# 19V_Converter.net
KiCad netlist of a schematic drawn in Altium Designer
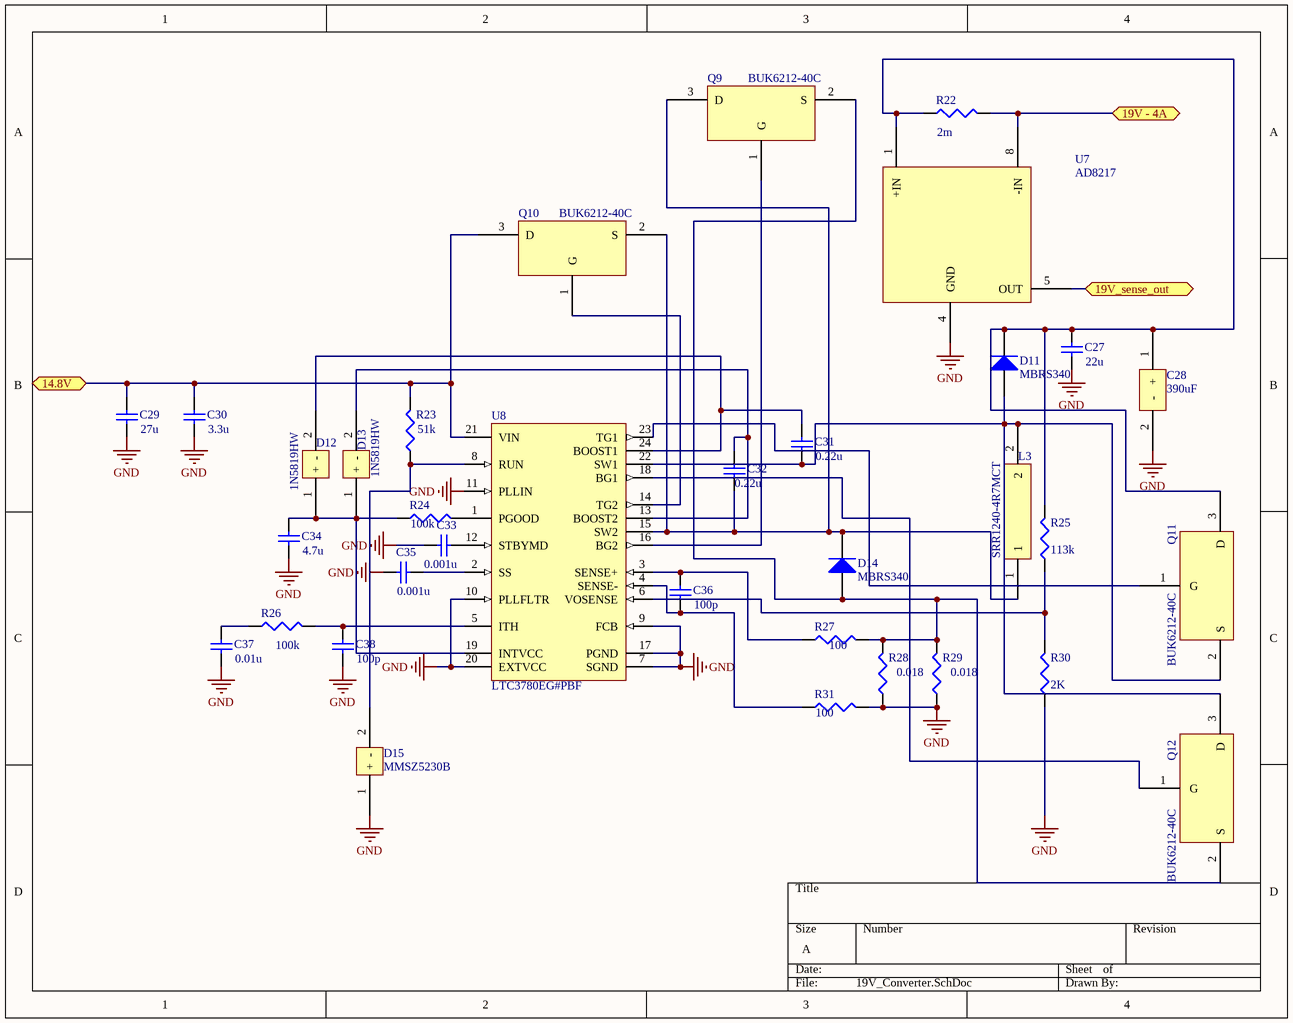
[diagram p0: 19V_Converter.SchDoc]

(export (version "E")
  (design (tool "Eeschema 10.0.6"))
  (components
    (comp (ref "C27")
      (value "22u")
      (footprint "C1206")
      (description "Capacitor (Semiconductor SIM Model)")
      (fields (field (name "Comment") "Cap Semi") (field (name "PUBLISHER") "Altium Limited"))
      (libsource (lib "Miscellaneous Devices") (part "Cap Semi"))
    )
    (comp (ref "C28")
      (value "390uF")
      (footprint "PCV1E391MCL2GS")
      (description "Aluminum Capacitor")
      (libsource (lib "Integrated_Library") (part "PCV1E391MCL2GS"))
    )
    (comp (ref "C29")
      (value "27u")
      (footprint "C1206")
      (description "Capacitor (Semiconductor SIM Model)")
      (fields (field (name "Comment") "Cap Semi") (field (name "PUBLISHER") "Altium Limited"))
      (libsource (lib "Miscellaneous Devices") (part "Cap Semi"))
    )
    (comp (ref "C30")
      (value "3.3u")
      (footprint "C1206")
      (description "Capacitor (Semiconductor SIM Model)")
      (fields (field (name "Comment") "Cap Semi") (field (name "PUBLISHER") "Altium Limited"))
      (libsource (lib "Miscellaneous Devices") (part "Cap Semi"))
    )
    (comp (ref "C31")
      (value "0.22u")
      (footprint "C1206")
      (description "Capacitor (Semiconductor SIM Model)")
      (fields (field (name "Comment") "Cap Semi") (field (name "PUBLISHER") "Altium Limited"))
      (libsource (lib "Miscellaneous Devices") (part "Cap Semi"))
    )
    (comp (ref "C32")
      (value "0.22u")
      (footprint "C1206")
      (description "Capacitor (Semiconductor SIM Model)")
      (fields (field (name "Comment") "Cap Semi") (field (name "PUBLISHER") "Altium Limited"))
      (libsource (lib "Miscellaneous Devices") (part "Cap Semi"))
    )
    (comp (ref "C33")
      (value "0.001u")
      (footprint "C1206")
      (description "Capacitor (Semiconductor SIM Model)")
      (fields (field (name "Comment") "Cap Semi") (field (name "PUBLISHER") "Altium Limited"))
      (libsource (lib "Miscellaneous Devices") (part "Cap Semi"))
    )
    (comp (ref "C34")
      (value "4.7u")
      (footprint "C1206")
      (description "Capacitor (Semiconductor SIM Model)")
      (fields (field (name "Comment") "Cap Semi") (field (name "PUBLISHER") "Altium Limited"))
      (libsource (lib "Miscellaneous Devices") (part "Cap Semi"))
    )
    (comp (ref "C35")
      (value "0.001u")
      (footprint "C1206")
      (description "Capacitor (Semiconductor SIM Model)")
      (fields (field (name "Comment") "Cap Semi") (field (name "PUBLISHER") "Altium Limited"))
      (libsource (lib "Miscellaneous Devices") (part "Cap Semi"))
    )
    (comp (ref "C36")
      (value "100p")
      (footprint "C1206")
      (description "Capacitor (Semiconductor SIM Model)")
      (fields (field (name "Comment") "Cap Semi") (field (name "PUBLISHER") "Altium Limited"))
      (libsource (lib "Miscellaneous Devices") (part "Cap Semi"))
    )
    (comp (ref "C37")
      (value "0.01u")
      (footprint "C1206")
      (description "Capacitor (Semiconductor SIM Model)")
      (fields (field (name "Comment") "Cap Semi") (field (name "PUBLISHER") "Altium Limited"))
      (libsource (lib "Miscellaneous Devices") (part "Cap Semi"))
    )
    (comp (ref "C38")
      (value "100p")
      (footprint "C1206")
      (description "Capacitor (Semiconductor SIM Model)")
      (fields (field (name "Comment") "Cap Semi") (field (name "PUBLISHER") "Altium Limited"))
      (libsource (lib "Miscellaneous Devices") (part "Cap Semi"))
    )
    (comp (ref "D11")
      (value "MBRS340")
      (footprint "SMC")
      (description "Default Diode")
      (fields (field (name "PUBLISHER") "Altium Limited"))
      (libsource (lib "Miscellaneous Devices") (part "Diode"))
    )
    (comp (ref "D12")
      (value "1N5819HW")
      (footprint "1N5819HW")
      (description "1A Schottky Barrier Rectifier")
      (libsource (lib "Integrated_Library") (part "1N5819HW"))
    )
    (comp (ref "D13")
      (value "1N5819HW")
      (footprint "1N5819HW")
      (description "1A Schottky Barrier Rectifier")
      (libsource (lib "Integrated_Library") (part "1N5819HW"))
    )
    (comp (ref "D14")
      (value "MBRS340")
      (footprint "SMC")
      (description "Default Diode")
      (fields (field (name "PUBLISHER") "Altium Limited"))
      (libsource (lib "Miscellaneous Devices") (part "Diode"))
    )
    (comp (ref "D15")
      (value "MMSZ5230B")
      (footprint "MMSZ5230B")
      (description "Zener Diode")
      (libsource (lib "Integrated_Library") (part "MMSZ5230B"))
    )
    (comp (ref "L3")
      (value "SRR1240-4R7MCT")
      (footprint "SRR1240-4R7M")
      (description "Inductor")
      (libsource (lib "Integrated_Library") (part "SRR1240-4R7MCT"))
    )
    (comp (ref "Q9")
      (value "BUK6212-40C")
      (footprint "BUK6212-40C")
      (description "N-Channel TrenchMOS Intermediate Level FET")
      (libsource (lib "Integrated_Library") (part "BUK6212-40C"))
    )
    (comp (ref "Q10")
      (value "BUK6212-40C")
      (footprint "BUK6212-40C")
      (description "N-Channel TrenchMOS Intermediate Level FET")
      (libsource (lib "Integrated_Library") (part "BUK6212-40C"))
    )
    (comp (ref "Q11")
      (value "BUK6212-40C")
      (footprint "BUK6212-40C")
      (description "N-Channel TrenchMOS Intermediate Level FET")
      (libsource (lib "") (part "BUK6212-40C_1"))
    )
    (comp (ref "Q12")
      (value "BUK6212-40C")
      (footprint "BUK6212-40C")
      (description "N-Channel TrenchMOS Intermediate Level FET")
      (libsource (lib "") (part "BUK6212-40C_1"))
    )
    (comp (ref "R22")
      (value "2m")
      (footprint "J1-0603")
      (description "Resistor")
      (fields (field (name "Comment") "Res3") (field (name "PUBLISHER") "Altium Limited"))
      (libsource (lib "Miscellaneous Devices") (part "Res3"))
    )
    (comp (ref "R23")
      (value "51k")
      (footprint "J1-0603")
      (description "Resistor")
      (fields (field (name "Comment") "Res3") (field (name "PUBLISHER") "Altium Limited"))
      (libsource (lib "Miscellaneous Devices") (part "Res3"))
    )
    (comp (ref "R24")
      (value "100k")
      (footprint "J1-0603")
      (description "Resistor")
      (fields (field (name "Comment") "Res3") (field (name "PUBLISHER") "Altium Limited"))
      (libsource (lib "Miscellaneous Devices") (part "Res3"))
    )
    (comp (ref "R25")
      (value "113k")
      (footprint "J1-0603")
      (description "Resistor")
      (fields (field (name "Comment") "Res3") (field (name "PUBLISHER") "Altium Limited"))
      (libsource (lib "Miscellaneous Devices") (part "Res3"))
    )
    (comp (ref "R26")
      (value "100k")
      (footprint "J1-0603")
      (description "Resistor")
      (fields (field (name "Comment") "Res3") (field (name "PUBLISHER") "Altium Limited"))
      (libsource (lib "Miscellaneous Devices") (part "Res3"))
    )
    (comp (ref "R27")
      (value "100")
      (footprint "J1-0603")
      (description "Resistor")
      (fields (field (name "Comment") "Res3") (field (name "PUBLISHER") "Altium Limited"))
      (libsource (lib "Miscellaneous Devices") (part "Res3"))
    )
    (comp (ref "R28")
      (value "0.018")
      (footprint "J1-0603")
      (description "Resistor")
      (fields (field (name "Comment") "Res3") (field (name "PUBLISHER") "Altium Limited"))
      (libsource (lib "Miscellaneous Devices") (part "Res3"))
    )
    (comp (ref "R29")
      (value "0.018")
      (footprint "J1-0603")
      (description "Resistor")
      (fields (field (name "Comment") "Res3") (field (name "PUBLISHER") "Altium Limited"))
      (libsource (lib "Miscellaneous Devices") (part "Res3"))
    )
    (comp (ref "R30")
      (value "2K")
      (footprint "J1-0603")
      (description "Resistor")
      (fields (field (name "Comment") "Res3") (field (name "PUBLISHER") "Altium Limited"))
      (libsource (lib "Miscellaneous Devices") (part "Res3"))
    )
    (comp (ref "R31")
      (value "100")
      (footprint "J1-0603")
      (description "Resistor")
      (fields (field (name "Comment") "Res3") (field (name "PUBLISHER") "Altium Limited"))
      (libsource (lib "Miscellaneous Devices") (part "Res3"))
    )
    (comp (ref "U7")
      (value "AD8217")
      (footprint "AD8217")
      (description "Current Shunt Moniter")
      (libsource (lib "Integrated_Library") (part "AD8217"))
    )
    (comp (ref "U8")
      (value "LTC3780EG#PBF")
      (footprint "LTC3780 24-Leaqd Plastic SSOP")
      (fields (field (name "MANUFACTURER") "Linear Technology"))
      (libsource (lib "Integrated_Library") (part "LTC3780EG#PBF"))
    )
  )
  (nets
    (net (code "1") (name "/14.8V") (class "Default")
      (node (ref "C29") (pin "2") (pinfunction "2_2") (pintype "passive"))
      (node (ref "C30") (pin "2") (pinfunction "2_2") (pintype "passive"))
      (node (ref "Q10") (pin "3") (pinfunction "D_3") (pintype "passive"))
      (node (ref "R23") (pin "2") (pinfunction "2_2") (pintype "passive"))
      (node (ref "U8") (pin "21") (pinfunction "VIN_21") (pintype "power_in"))
    )
    (net (code "2") (name "/19V - 4A") (class "Default")
      (node (ref "R22") (pin "2") (pinfunction "2_2") (pintype "passive"))
      (node (ref "U7") (pin "8") (pinfunction "-IN_8") (pintype "passive"))
    )
    (net (code "3") (name "/19V_sense_out") (class "Default")
      (node (ref "U7") (pin "5") (pinfunction "OUT_5") (pintype "passive"))
    )
    (net (code "4") (name "GND") (class "Default")
      (node (ref "C27") (pin "1") (pinfunction "1_1") (pintype "passive"))
      (node (ref "C28") (pin "2") (pinfunction "-_2") (pintype "passive"))
      (node (ref "C29") (pin "1") (pinfunction "1_1") (pintype "passive"))
      (node (ref "C30") (pin "1") (pinfunction "1_1") (pintype "passive"))
      (node (ref "C33") (pin "1") (pinfunction "1_1") (pintype "passive"))
      (node (ref "C34") (pin "1") (pinfunction "1_1") (pintype "passive"))
      (node (ref "C35") (pin "1") (pinfunction "1_1") (pintype "passive"))
      (node (ref "C37") (pin "1") (pinfunction "1_1") (pintype "passive"))
      (node (ref "C38") (pin "1") (pinfunction "1_1") (pintype "passive"))
      (node (ref "D15") (pin "1") (pinfunction "+_1") (pintype "passive"))
      (node (ref "R28") (pin "1") (pinfunction "1_1") (pintype "passive"))
      (node (ref "R29") (pin "1") (pinfunction "1_1") (pintype "passive"))
      (node (ref "R30") (pin "1") (pinfunction "1_1") (pintype "passive"))
      (node (ref "R31") (pin "2") (pinfunction "2_2") (pintype "passive"))
      (node (ref "U7") (pin "4") (pinfunction "GND_4") (pintype "passive"))
      (node (ref "U8") (pin "10") (pinfunction "PLLFLTR_10") (pintype "input"))
      (node (ref "U8") (pin "11") (pinfunction "PLLIN_11") (pintype "input"))
      (node (ref "U8") (pin "17") (pinfunction "PGND_17") (pintype "power_in"))
      (node (ref "U8") (pin "20") (pinfunction "EXTVCC_20") (pintype "power_in"))
      (node (ref "U8") (pin "7") (pinfunction "SGND_7") (pintype "power_in"))
      (node (ref "U8") (pin "9") (pinfunction "FCB_9") (pintype "input"))
    )
    (net (code "5") (name "Net-(C28-+)") (class "Default")
      (node (ref "C27") (pin "2") (pinfunction "2_2") (pintype "passive"))
      (node (ref "C28") (pin "1") (pinfunction "+_1") (pintype "passive"))
      (node (ref "D11") (pin "2") (pinfunction "K_2") (pintype "passive"))
      (node (ref "Q11") (pin "3") (pinfunction "D_3") (pintype "passive"))
      (node (ref "R22") (pin "1") (pinfunction "1_1") (pintype "passive"))
      (node (ref "R25") (pin "2") (pinfunction "2_2") (pintype "passive"))
      (node (ref "U7") (pin "1") (pinfunction "+IN_1") (pintype "passive"))
    )
    (net (code "6") (name "Net-(C37-Pad2)") (class "Default")
      (node (ref "C37") (pin "2") (pinfunction "2_2") (pintype "passive"))
      (node (ref "R26") (pin "1") (pinfunction "1_1") (pintype "passive"))
    )
    (net (code "7") (name "Net-(D11-A)") (class "Default")
      (node (ref "C31") (pin "1") (pinfunction "1_1") (pintype "passive"))
      (node (ref "D11") (pin "1") (pinfunction "A_1") (pintype "passive"))
      (node (ref "L3") (pin "2") (pinfunction "2_2") (pintype "passive"))
      (node (ref "Q11") (pin "2") (pinfunction "S_2") (pintype "passive"))
      (node (ref "Q12") (pin "3") (pinfunction "D_3") (pintype "passive"))
      (node (ref "U8") (pin "22") (pinfunction "SW1_22") (pintype "passive"))
    )
    (net (code "8") (name "Net-(D12-+)") (class "Default")
      (node (ref "C34") (pin "2") (pinfunction "2_2") (pintype "passive"))
      (node (ref "D12") (pin "1") (pinfunction "+_1") (pintype "passive"))
      (node (ref "D13") (pin "1") (pinfunction "+_1") (pintype "passive"))
      (node (ref "R24") (pin "1") (pinfunction "1_1") (pintype "passive"))
      (node (ref "U8") (pin "19") (pinfunction "INTVCC_19") (pintype "power_in"))
    )
    (net (code "9") (name "Net-(D12--)") (class "Default")
      (node (ref "C31") (pin "2") (pinfunction "2_2") (pintype "passive"))
      (node (ref "D12") (pin "2") (pinfunction "-_2") (pintype "passive"))
      (node (ref "U8") (pin "24") (pinfunction "BOOST1_24") (pintype "passive"))
    )
    (net (code "10") (name "Net-(D13--)") (class "Default")
      (node (ref "C32") (pin "2") (pinfunction "2_2") (pintype "passive"))
      (node (ref "D13") (pin "2") (pinfunction "-_2") (pintype "passive"))
      (node (ref "U8") (pin "13") (pinfunction "BOOST2_13") (pintype "passive"))
    )
    (net (code "11") (name "Net-(D14-A)") (class "Default")
      (node (ref "D14") (pin "1") (pinfunction "A_1") (pintype "passive"))
      (node (ref "Q12") (pin "2") (pinfunction "S_2") (pintype "passive"))
      (node (ref "Q9") (pin "2") (pinfunction "S_2") (pintype "passive"))
      (node (ref "R27") (pin "2") (pinfunction "2_2") (pintype "passive"))
      (node (ref "R28") (pin "2") (pinfunction "2_2") (pintype "passive"))
      (node (ref "R29") (pin "2") (pinfunction "2_2") (pintype "passive"))
    )
    (net (code "12") (name "Net-(D14-K)") (class "Default")
      (node (ref "C32") (pin "1") (pinfunction "1_1") (pintype "passive"))
      (node (ref "D14") (pin "2") (pinfunction "K_2") (pintype "passive"))
      (node (ref "L3") (pin "1") (pinfunction "1_1") (pintype "passive"))
      (node (ref "Q10") (pin "2") (pinfunction "S_2") (pintype "passive"))
      (node (ref "Q9") (pin "3") (pinfunction "D_3") (pintype "passive"))
      (node (ref "U8") (pin "15") (pinfunction "SW2_15") (pintype "passive"))
    )
    (net (code "13") (name "Net-(D15--)") (class "Default")
      (node (ref "D15") (pin "2") (pinfunction "-_2") (pintype "passive"))
      (node (ref "R23") (pin "1") (pinfunction "1_1") (pintype "passive"))
      (node (ref "U8") (pin "8") (pinfunction "RUN_8") (pintype "input"))
    )
    (net (code "14") (name "Net-(Q9-G)") (class "Default")
      (node (ref "Q9") (pin "1") (pinfunction "G_1") (pintype "passive"))
      (node (ref "U8") (pin "16") (pinfunction "BG2_16") (pintype "output"))
    )
    (net (code "15") (name "Net-(Q10-G)") (class "Default")
      (node (ref "Q10") (pin "1") (pinfunction "G_1") (pintype "passive"))
      (node (ref "U8") (pin "14") (pinfunction "TG2_14") (pintype "output"))
    )
    (net (code "16") (name "Net-(Q11-G)") (class "Default")
      (node (ref "Q11") (pin "1") (pinfunction "G_1") (pintype "passive"))
      (node (ref "U8") (pin "23") (pinfunction "TG1_23") (pintype "output"))
    )
    (net (code "17") (name "Net-(Q12-G)") (class "Default")
      (node (ref "Q12") (pin "1") (pinfunction "G_1") (pintype "passive"))
      (node (ref "U8") (pin "18") (pinfunction "BG1_18") (pintype "output"))
    )
    (net (code "18") (name "Net-(U8-ITH)") (class "Default")
      (node (ref "C38") (pin "2") (pinfunction "2_2") (pintype "passive"))
      (node (ref "R26") (pin "2") (pinfunction "2_2") (pintype "passive"))
      (node (ref "U8") (pin "5") (pinfunction "ITH_5") (pintype "passive"))
    )
    (net (code "19") (name "Net-(U8-PGOOD)") (class "Default")
      (node (ref "R24") (pin "2") (pinfunction "2_2") (pintype "passive"))
      (node (ref "U8") (pin "1") (pinfunction "PGOOD_1") (pintype "open_collector"))
    )
    (net (code "20") (name "Net-(U8-SENSE+)") (class "Default")
      (node (ref "C36") (pin "2") (pinfunction "2_2") (pintype "passive"))
      (node (ref "R27") (pin "1") (pinfunction "1_1") (pintype "passive"))
      (node (ref "U8") (pin "3") (pinfunction "SENSE+_3") (pintype "input"))
    )
    (net (code "21") (name "Net-(U8-SENSE-)") (class "Default")
      (node (ref "C36") (pin "1") (pinfunction "1_1") (pintype "passive"))
      (node (ref "R31") (pin "1") (pinfunction "1_1") (pintype "passive"))
      (node (ref "U8") (pin "4") (pinfunction "SENSE-_4") (pintype "input"))
    )
    (net (code "22") (name "Net-(U8-SS)") (class "Default")
      (node (ref "C35") (pin "2") (pinfunction "2_2") (pintype "passive"))
      (node (ref "U8") (pin "2") (pinfunction "SS_2") (pintype "input"))
    )
    (net (code "23") (name "Net-(U8-STBYMD)") (class "Default")
      (node (ref "C33") (pin "2") (pinfunction "2_2") (pintype "passive"))
      (node (ref "U8") (pin "12") (pinfunction "STBYMD_12") (pintype "input"))
    )
    (net (code "24") (name "Net-(U8-VOSENSE)") (class "Default")
      (node (ref "R25") (pin "1") (pinfunction "1_1") (pintype "passive"))
      (node (ref "R30") (pin "2") (pinfunction "2_2") (pintype "passive"))
      (node (ref "U8") (pin "6") (pinfunction "VOSENSE_6") (pintype "input"))
    )
  )
)
